# Sheet2.net
KiCad netlist of a schematic drawn in Altium Designer
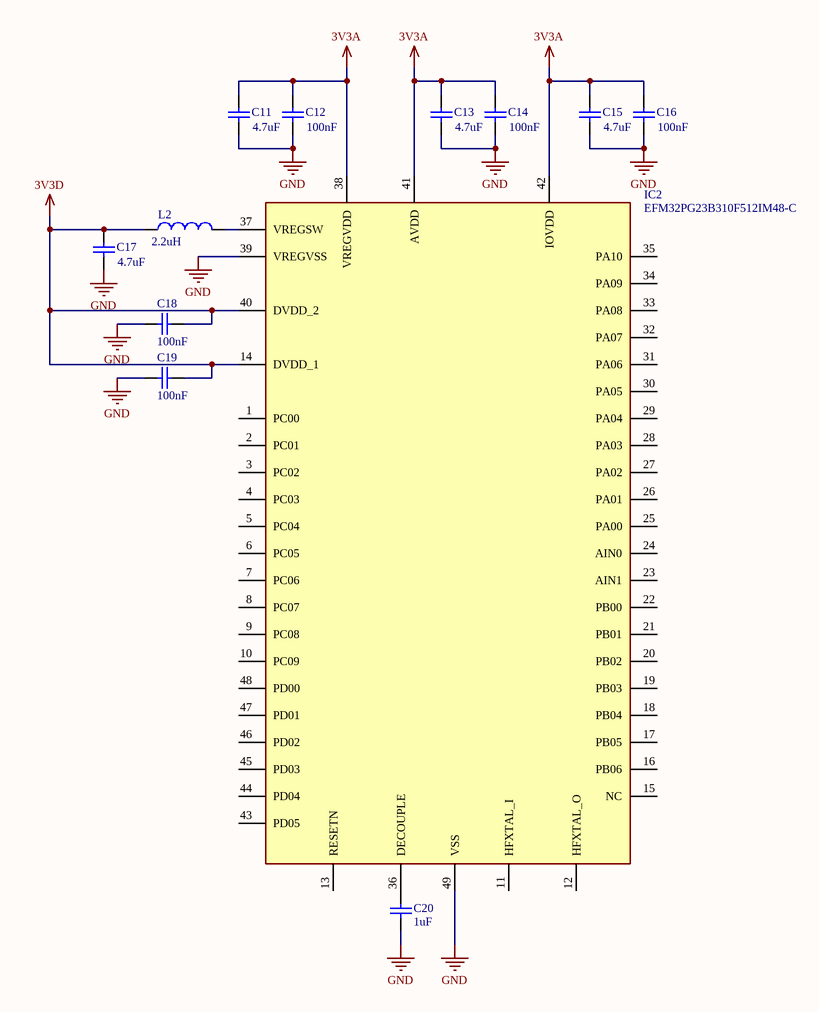
[diagram p0: Sheet2.SchDoc]

(export (version "E")
  (design (tool "Eeschema 10.0.6"))
  (components
    (comp (ref "C11")
      (value "4.7uF")
      (footprint "CAPC1608X92X38LL15T08")
      (fields (field (name "MANUFACTURER") "Vitramon") (field (name "PART NUMBER") "VJ0603D3R9CXPAJ"))
      (libsource (lib "Altium Content Vault") (part "CAP"))
    )
    (comp (ref "C12")
      (value "100nF")
      (footprint "CAPC1608X92X38LL15T08")
      (fields (field (name "MANUFACTURER") "Vitramon") (field (name "PART NUMBER") "VJ0603D3R9CXPAJ"))
      (libsource (lib "Altium Content Vault") (part "CAP"))
    )
    (comp (ref "C13")
      (value "4.7uF")
      (footprint "CAPC1608X92X38LL15T08")
      (fields (field (name "MANUFACTURER") "Vitramon") (field (name "PART NUMBER") "VJ0603D3R9CXPAJ"))
      (libsource (lib "Altium Content Vault") (part "CAP"))
    )
    (comp (ref "C14")
      (value "100nF")
      (footprint "CAPC1608X92X38LL15T08")
      (fields (field (name "MANUFACTURER") "Vitramon") (field (name "PART NUMBER") "VJ0603D3R9CXPAJ"))
      (libsource (lib "Altium Content Vault") (part "CAP"))
    )
    (comp (ref "C15")
      (value "4.7uF")
      (footprint "CAPC1608X92X38LL15T08")
      (fields (field (name "MANUFACTURER") "Vitramon") (field (name "PART NUMBER") "VJ0603D3R9CXPAJ"))
      (libsource (lib "Altium Content Vault") (part "CAP"))
    )
    (comp (ref "C16")
      (value "100nF")
      (footprint "CAPC1608X92X38LL15T08")
      (fields (field (name "MANUFACTURER") "Vitramon") (field (name "PART NUMBER") "VJ0603D3R9CXPAJ"))
      (libsource (lib "Altium Content Vault") (part "CAP"))
    )
    (comp (ref "C17")
      (value "4.7uF")
      (footprint "CAPC1608X92X38LL15T08")
      (fields (field (name "MANUFACTURER") "Vitramon") (field (name "PART NUMBER") "VJ0603D3R9CXPAJ"))
      (libsource (lib "Altium Content Vault") (part "CAP"))
    )
    (comp (ref "C18")
      (value "100nF")
      (footprint "CAPC1608X92X38LL15T08")
      (fields (field (name "MANUFACTURER") "Vitramon") (field (name "PART NUMBER") "VJ0603D3R9CXPAJ"))
      (libsource (lib "Altium Content Vault") (part "CAP"))
    )
    (comp (ref "C19")
      (value "100nF")
      (footprint "CAPC1608X92X38LL15T08")
      (fields (field (name "MANUFACTURER") "Vitramon") (field (name "PART NUMBER") "VJ0603D3R9CXPAJ"))
      (libsource (lib "Altium Content Vault") (part "CAP"))
    )
    (comp (ref "C20")
      (value "1uF")
      (footprint "CAPC1608X92X38LL15T08")
      (fields (field (name "MANUFACTURER") "Vitramon") (field (name "PART NUMBER") "VJ0603D3R9CXPAJ"))
      (libsource (lib "Altium Content Vault") (part "CAP"))
    )
    (comp (ref "IC2")
      (value "EFM32PG23B310F512IM48-C")
      (footprint "SamacSys:QFN40P600X600X90-49N-D")
      (description "Integrated Circuit")
      (fields (field (name "MOUSER PART NUMBER") "634-PG23310F512IM48C"))
      (libsource (lib "SamacSys") (part "EFM32PG23B310F512IM48-C"))
    )
    (comp (ref "L2")
      (value "7447860115G")
      (footprint "WE-MK_0603_L1.6W0.8H0.8")
      (fields (field (name "INDUCTANCE") "2.2uH"))
      (libsource (lib "Altium Content Vault") (part "Inductor - 1"))
    )
  )
  (nets
    (net (code "1") (name "3V3A") (class "Default")
      (node (ref "C11") (pin "2") (pinfunction "2_2") (pintype "passive"))
      (node (ref "C12") (pin "2") (pinfunction "2_2") (pintype "passive"))
      (node (ref "C13") (pin "2") (pinfunction "2_2") (pintype "passive"))
      (node (ref "C14") (pin "2") (pinfunction "2_2") (pintype "passive"))
      (node (ref "C15") (pin "2") (pinfunction "2_2") (pintype "passive"))
      (node (ref "C16") (pin "2") (pinfunction "2_2") (pintype "passive"))
      (node (ref "IC2") (pin "38") (pinfunction "VREGVDD_38") (pintype "passive"))
      (node (ref "IC2") (pin "41") (pinfunction "AVDD_41") (pintype "passive"))
      (node (ref "IC2") (pin "42") (pinfunction "IOVDD_42") (pintype "passive"))
    )
    (net (code "2") (name "3V3D") (class "Default")
      (node (ref "C17") (pin "2") (pinfunction "2_2") (pintype "passive"))
      (node (ref "C18") (pin "1") (pinfunction "1_1") (pintype "passive"))
      (node (ref "C19") (pin "1") (pinfunction "1_1") (pintype "passive"))
      (node (ref "IC2") (pin "14") (pinfunction "DVDD_1_14") (pintype "passive"))
      (node (ref "IC2") (pin "40") (pinfunction "DVDD_2_40") (pintype "passive"))
      (node (ref "L2") (pin "1") (pinfunction "1_1") (pintype "passive"))
    )
    (net (code "3") (name "GND") (class "Default")
      (node (ref "C11") (pin "1") (pinfunction "1_1") (pintype "passive"))
      (node (ref "C12") (pin "1") (pinfunction "1_1") (pintype "passive"))
      (node (ref "C13") (pin "1") (pinfunction "1_1") (pintype "passive"))
      (node (ref "C14") (pin "1") (pinfunction "1_1") (pintype "passive"))
      (node (ref "C15") (pin "1") (pinfunction "1_1") (pintype "passive"))
      (node (ref "C16") (pin "1") (pinfunction "1_1") (pintype "passive"))
      (node (ref "C17") (pin "1") (pinfunction "1_1") (pintype "passive"))
      (node (ref "C18") (pin "2") (pinfunction "2_2") (pintype "passive"))
      (node (ref "C19") (pin "2") (pinfunction "2_2") (pintype "passive"))
      (node (ref "C20") (pin "2") (pinfunction "2_2") (pintype "passive"))
      (node (ref "IC2") (pin "39") (pinfunction "VREGVSS_39") (pintype "passive"))
      (node (ref "IC2") (pin "49") (pinfunction "VSS_49") (pintype "passive"))
    )
    (net (code "4") (name "Net-(IC2-DECOUPLE)") (class "Default")
      (node (ref "C20") (pin "1") (pinfunction "1_1") (pintype "passive"))
      (node (ref "IC2") (pin "36") (pinfunction "DECOUPLE_36") (pintype "passive"))
    )
    (net (code "5") (name "Net-(IC2-VREGSW)") (class "Default")
      (node (ref "IC2") (pin "37") (pinfunction "VREGSW_37") (pintype "passive"))
      (node (ref "L2") (pin "2") (pinfunction "2_2") (pintype "passive"))
    )
    (net (code "6") (name "unconnected-(IC2-AIN0-Pad24)") (class "Default")
      (node (ref "IC2") (pin "24") (pinfunction "AIN0_24") (pintype "passive"))
    )
    (net (code "7") (name "unconnected-(IC2-AIN1-Pad23)") (class "Default")
      (node (ref "IC2") (pin "23") (pinfunction "AIN1_23") (pintype "passive"))
    )
    (net (code "8") (name "unconnected-(IC2-HFXTAL_I-Pad11)") (class "Default")
      (node (ref "IC2") (pin "11") (pinfunction "HFXTAL_I_11") (pintype "passive"))
    )
    (net (code "9") (name "unconnected-(IC2-HFXTAL_O-Pad12)") (class "Default")
      (node (ref "IC2") (pin "12") (pinfunction "HFXTAL_O_12") (pintype "passive"))
    )
    (net (code "10") (name "unconnected-(IC2-NC-Pad15)") (class "Default")
      (node (ref "IC2") (pin "15") (pinfunction "NC_15") (pintype "passive"))
    )
    (net (code "11") (name "unconnected-(IC2-PA00-Pad25)") (class "Default")
      (node (ref "IC2") (pin "25") (pinfunction "PA00_25") (pintype "passive"))
    )
    (net (code "12") (name "unconnected-(IC2-PA01-Pad26)") (class "Default")
      (node (ref "IC2") (pin "26") (pinfunction "PA01_26") (pintype "passive"))
    )
    (net (code "13") (name "unconnected-(IC2-PA02-Pad27)") (class "Default")
      (node (ref "IC2") (pin "27") (pinfunction "PA02_27") (pintype "passive"))
    )
    (net (code "14") (name "unconnected-(IC2-PA03-Pad28)") (class "Default")
      (node (ref "IC2") (pin "28") (pinfunction "PA03_28") (pintype "passive"))
    )
    (net (code "15") (name "unconnected-(IC2-PA04-Pad29)") (class "Default")
      (node (ref "IC2") (pin "29") (pinfunction "PA04_29") (pintype "passive"))
    )
    (net (code "16") (name "unconnected-(IC2-PA05-Pad30)") (class "Default")
      (node (ref "IC2") (pin "30") (pinfunction "PA05_30") (pintype "passive"))
    )
    (net (code "17") (name "unconnected-(IC2-PA06-Pad31)") (class "Default")
      (node (ref "IC2") (pin "31") (pinfunction "PA06_31") (pintype "passive"))
    )
    (net (code "18") (name "unconnected-(IC2-PA07-Pad32)") (class "Default")
      (node (ref "IC2") (pin "32") (pinfunction "PA07_32") (pintype "passive"))
    )
    (net (code "19") (name "unconnected-(IC2-PA08-Pad33)") (class "Default")
      (node (ref "IC2") (pin "33") (pinfunction "PA08_33") (pintype "passive"))
    )
    (net (code "20") (name "unconnected-(IC2-PA09-Pad34)") (class "Default")
      (node (ref "IC2") (pin "34") (pinfunction "PA09_34") (pintype "passive"))
    )
    (net (code "21") (name "unconnected-(IC2-PA10-Pad35)") (class "Default")
      (node (ref "IC2") (pin "35") (pinfunction "PA10_35") (pintype "passive"))
    )
    (net (code "22") (name "unconnected-(IC2-PB00-Pad22)") (class "Default")
      (node (ref "IC2") (pin "22") (pinfunction "PB00_22") (pintype "passive"))
    )
    (net (code "23") (name "unconnected-(IC2-PB01-Pad21)") (class "Default")
      (node (ref "IC2") (pin "21") (pinfunction "PB01_21") (pintype "passive"))
    )
    (net (code "24") (name "unconnected-(IC2-PB02-Pad20)") (class "Default")
      (node (ref "IC2") (pin "20") (pinfunction "PB02_20") (pintype "passive"))
    )
    (net (code "25") (name "unconnected-(IC2-PB03-Pad19)") (class "Default")
      (node (ref "IC2") (pin "19") (pinfunction "PB03_19") (pintype "passive"))
    )
    (net (code "26") (name "unconnected-(IC2-PB04-Pad18)") (class "Default")
      (node (ref "IC2") (pin "18") (pinfunction "PB04_18") (pintype "passive"))
    )
    (net (code "27") (name "unconnected-(IC2-PB05-Pad17)") (class "Default")
      (node (ref "IC2") (pin "17") (pinfunction "PB05_17") (pintype "passive"))
    )
    (net (code "28") (name "unconnected-(IC2-PB06-Pad16)") (class "Default")
      (node (ref "IC2") (pin "16") (pinfunction "PB06_16") (pintype "passive"))
    )
    (net (code "29") (name "unconnected-(IC2-PC00-Pad1)") (class "Default")
      (node (ref "IC2") (pin "1") (pinfunction "PC00_1") (pintype "passive"))
    )
    (net (code "30") (name "unconnected-(IC2-PC01-Pad2)") (class "Default")
      (node (ref "IC2") (pin "2") (pinfunction "PC01_2") (pintype "passive"))
    )
    (net (code "31") (name "unconnected-(IC2-PC02-Pad3)") (class "Default")
      (node (ref "IC2") (pin "3") (pinfunction "PC02_3") (pintype "passive"))
    )
    (net (code "32") (name "unconnected-(IC2-PC03-Pad4)") (class "Default")
      (node (ref "IC2") (pin "4") (pinfunction "PC03_4") (pintype "passive"))
    )
    (net (code "33") (name "unconnected-(IC2-PC04-Pad5)") (class "Default")
      (node (ref "IC2") (pin "5") (pinfunction "PC04_5") (pintype "passive"))
    )
    (net (code "34") (name "unconnected-(IC2-PC05-Pad6)") (class "Default")
      (node (ref "IC2") (pin "6") (pinfunction "PC05_6") (pintype "passive"))
    )
    (net (code "35") (name "unconnected-(IC2-PC06-Pad7)") (class "Default")
      (node (ref "IC2") (pin "7") (pinfunction "PC06_7") (pintype "passive"))
    )
    (net (code "36") (name "unconnected-(IC2-PC07-Pad8)") (class "Default")
      (node (ref "IC2") (pin "8") (pinfunction "PC07_8") (pintype "passive"))
    )
    (net (code "37") (name "unconnected-(IC2-PC08-Pad9)") (class "Default")
      (node (ref "IC2") (pin "9") (pinfunction "PC08_9") (pintype "passive"))
    )
    (net (code "38") (name "unconnected-(IC2-PC09-Pad10)") (class "Default")
      (node (ref "IC2") (pin "10") (pinfunction "PC09_10") (pintype "passive"))
    )
    (net (code "39") (name "unconnected-(IC2-PD00-Pad48)") (class "Default")
      (node (ref "IC2") (pin "48") (pinfunction "PD00_48") (pintype "passive"))
    )
    (net (code "40") (name "unconnected-(IC2-PD01-Pad47)") (class "Default")
      (node (ref "IC2") (pin "47") (pinfunction "PD01_47") (pintype "passive"))
    )
    (net (code "41") (name "unconnected-(IC2-PD02-Pad46)") (class "Default")
      (node (ref "IC2") (pin "46") (pinfunction "PD02_46") (pintype "passive"))
    )
    (net (code "42") (name "unconnected-(IC2-PD03-Pad45)") (class "Default")
      (node (ref "IC2") (pin "45") (pinfunction "PD03_45") (pintype "passive"))
    )
    (net (code "43") (name "unconnected-(IC2-PD04-Pad44)") (class "Default")
      (node (ref "IC2") (pin "44") (pinfunction "PD04_44") (pintype "passive"))
    )
    (net (code "44") (name "unconnected-(IC2-PD05-Pad43)") (class "Default")
      (node (ref "IC2") (pin "43") (pinfunction "PD05_43") (pintype "passive"))
    )
    (net (code "45") (name "unconnected-(IC2-RESETN-Pad13)") (class "Default")
      (node (ref "IC2") (pin "13") (pinfunction "RESETN_13") (pintype "passive"))
    )
  )
)
